# LoRa_V.net
KiCad netlist of a schematic drawn in Altium Designer
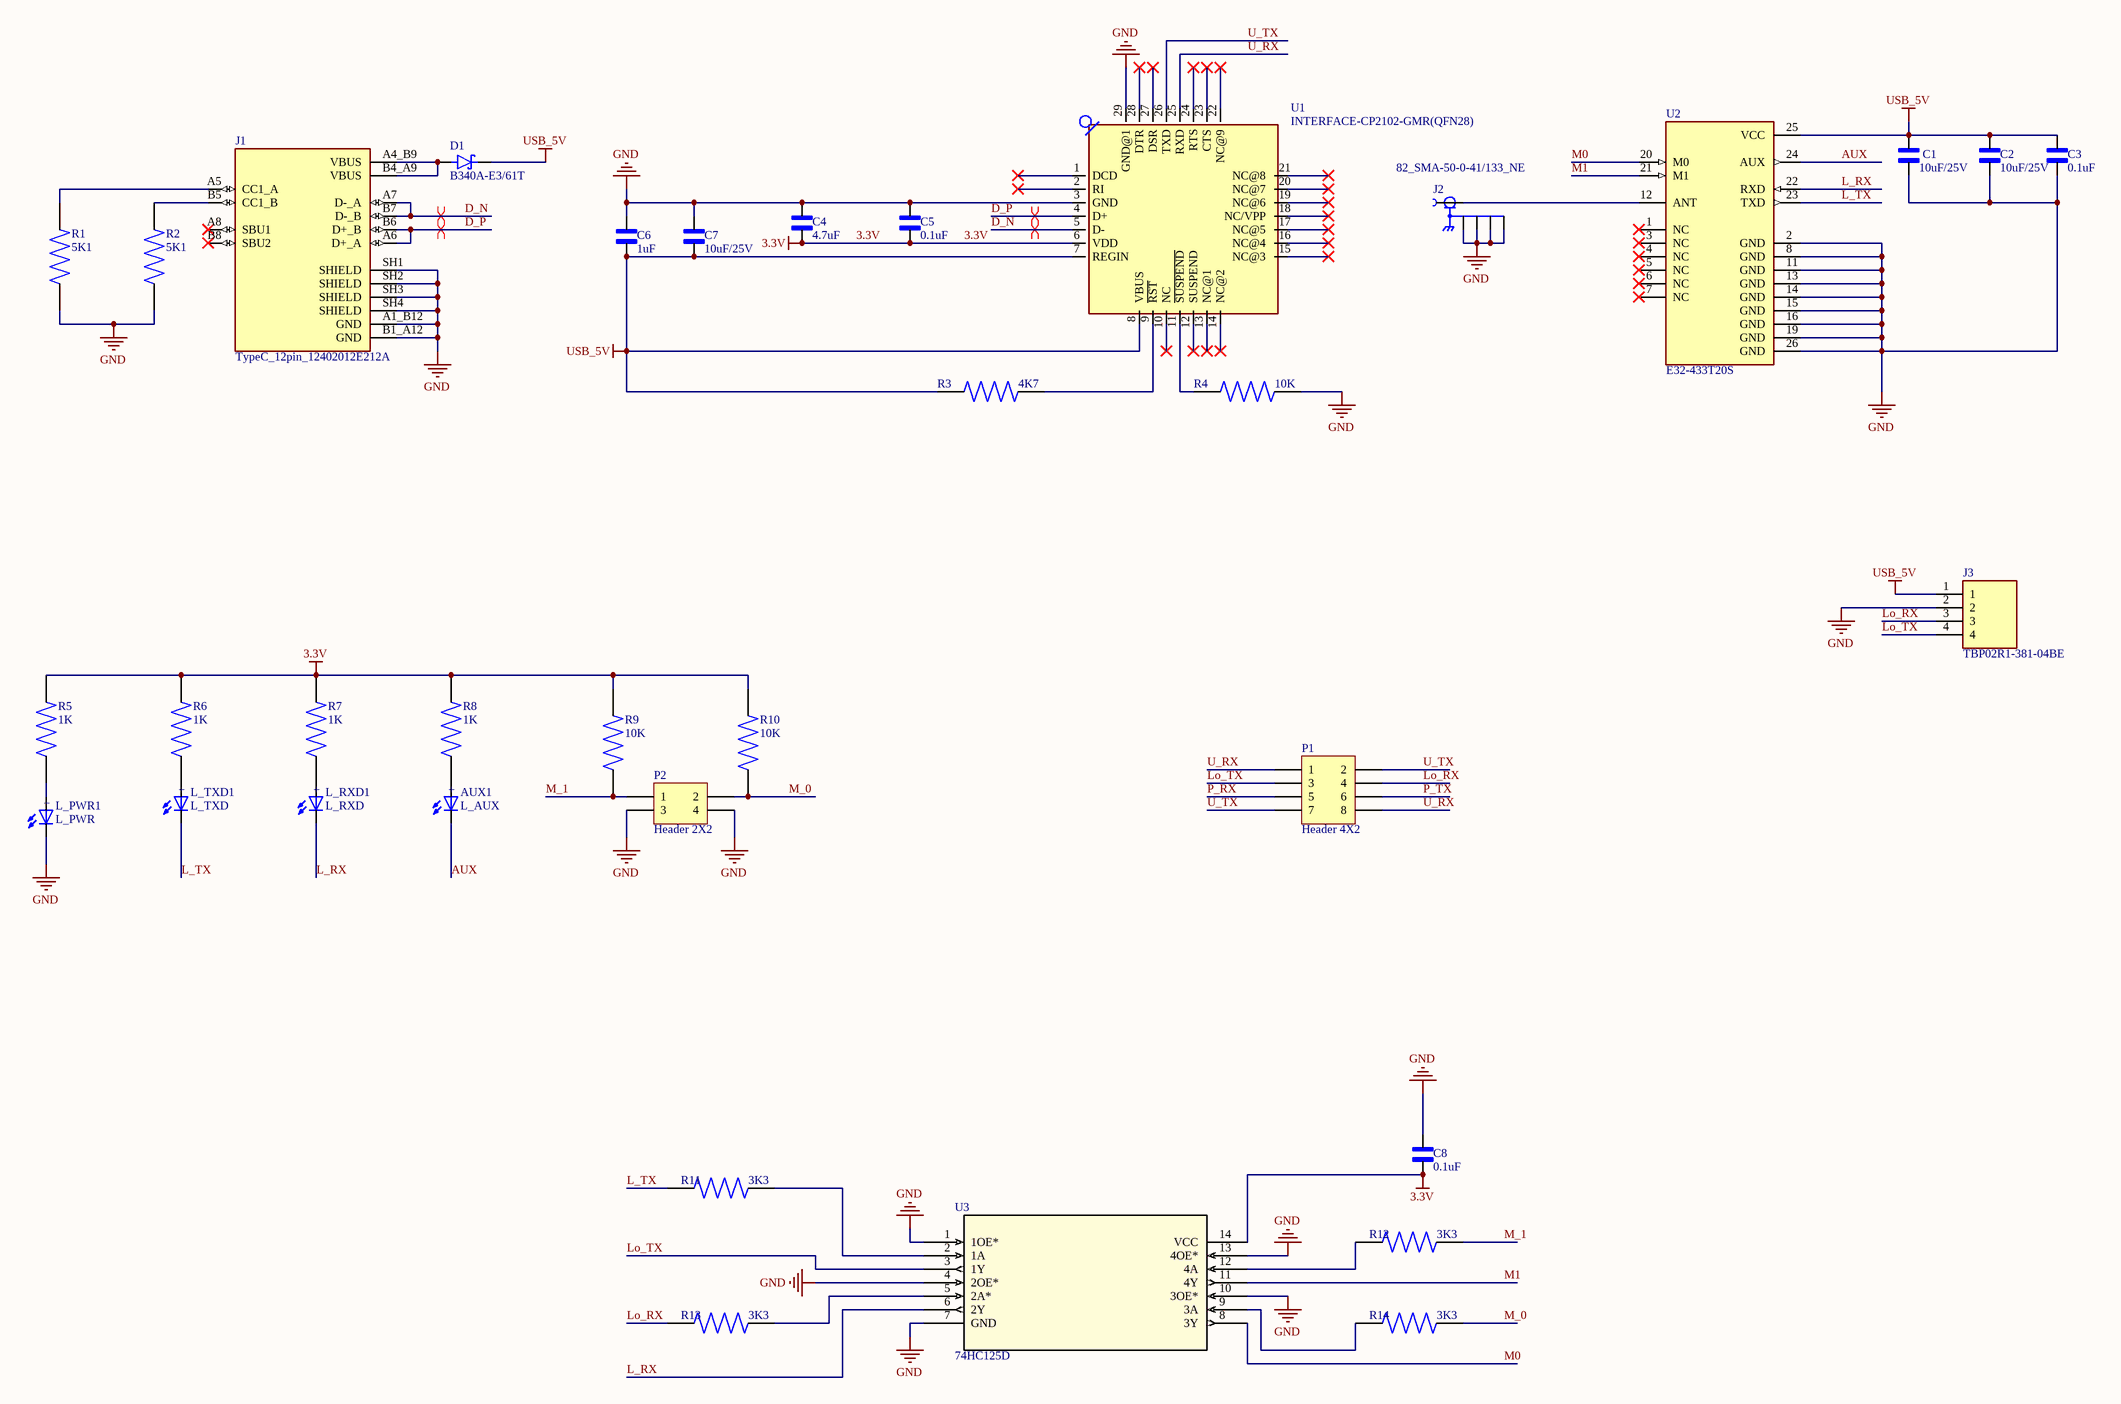
[diagram p0: LoRa_V.SchDoc]

(export (version "E")
  (design (tool "Eeschema 10.0.6"))
  (components
    (comp (ref "AUX1")
      (value "L_AUX")
      (footprint "WL-SMCW_1206")
      (description "1206, Blue Typ.(@20mA): 470nm, 145mcd, 3.2V, 140Â° InGaN")
      (fields (field (name "MF") "Wurth Electronics") (field (name "MP") "150120BS75000"))
      (libsource (lib "VIETTIEN") (part "WL-SMCW_1206"))
    )
    (comp (ref "C1")
      (value "10uF/25V")
      (footprint "CAPC1608X94N")
      (description "cap 0603 (1608 Metric)")
      (fields (field (name "MF") "Vishay Vitramon") (field (name "MP") "VJ0603D3R9DXCAP"))
      (libsource (lib "") (part "cap_0603_VJ0603D3R9DXCAP_1"))
    )
    (comp (ref "C2")
      (value "10uF/25V")
      (footprint "CAPC1608X94N")
      (description "cap 0603 (1608 Metric)")
      (fields (field (name "MF") "Vishay Vitramon") (field (name "MP") "VJ0603D3R9DXCAP"))
      (libsource (lib "") (part "cap_0603_VJ0603D3R9DXCAP_1"))
    )
    (comp (ref "C3")
      (value "0.1uF")
      (footprint "CAPC1608X94N")
      (description "cap 0603 (1608 Metric)")
      (fields (field (name "MF") "Vishay Vitramon") (field (name "MP") "VJ0603D3R9DXCAP"))
      (libsource (lib "") (part "cap_0603_VJ0603D3R9DXCAP_1"))
    )
    (comp (ref "C4")
      (value "4.7uF")
      (footprint "CAPC1608X94N")
      (description "cap 0603 (1608 Metric)")
      (fields (field (name "MF") "Vishay Vitramon") (field (name "MP") "VJ0603D3R9DXCAP"))
      (libsource (lib "") (part "cap_0603_VJ0603D3R9DXCAP_1"))
    )
    (comp (ref "C5")
      (value "0.1uF")
      (footprint "CAPC1608X94N")
      (description "cap 0603 (1608 Metric)")
      (fields (field (name "MF") "Vishay Vitramon") (field (name "MP") "VJ0603D3R9DXCAP"))
      (libsource (lib "") (part "cap_0603_VJ0603D3R9DXCAP_1"))
    )
    (comp (ref "C6")
      (value "1uF")
      (footprint "CAPC1608X94N")
      (description "cap 0603 (1608 Metric)")
      (fields (field (name "MF") "Vishay Vitramon") (field (name "MP") "VJ0603D3R9DXCAP"))
      (libsource (lib "") (part "cap_0603_VJ0603D3R9DXCAP_1"))
    )
    (comp (ref "C7")
      (value "10uF/25V")
      (footprint "CAPC1608X94N")
      (description "cap 0603 (1608 Metric)")
      (fields (field (name "MF") "Vishay Vitramon") (field (name "MP") "VJ0603D3R9DXCAP"))
      (libsource (lib "") (part "cap_0603_VJ0603D3R9DXCAP_1"))
    )
    (comp (ref "C8")
      (value "0.1uF")
      (footprint "CAPC1608X94N")
      (description "cap 0603 (1608 Metric)")
      (fields (field (name "MF") "Vishay Vitramon") (field (name "MP") "VJ0603D3R9DXCAP"))
      (libsource (lib "VIETTIEN") (part "cap_0603_VJ0603D3R9DXCAP"))
    )
    (comp (ref "D1")
      (value "B340A-E3/61T")
      (footprint "DIOM5126X229N")
      (description "Diode Schottky 40 V 3A Surface Mount DO-214AC (SMA)")
      (fields (field (name "MF") "Vishay Semiconductor"))
      (libsource (lib "VIETTIEN") (part "B340A-E3/61T"))
    )
    (comp (ref "J1")
      (value "TypeC_12pin_12402012E212A")
      (footprint "TypeC_12pin_12402012E212A")
      (description "USB2.0, Type C, Top mount, CH 1.68mm, Dual Row SMT")
      (fields (field (name "MP") "12402012E212A") (field (name "MF") "Amphenol ICC (Commercial Products)"))
      (libsource (lib "VIETTIEN") (part "TypeC_12pin_12402012E212A"))
    )
    (comp (ref "J2")
      (value "82_SMA-50-0-41/133_NE")
      (footprint "HUBER+SUHNER_82_SMA-50-0-41/133_NE")
      (description "RF Connectors / Coaxial Connectors, Straight Pcb Jack ¦ HUBER+SUHNER 82_SMA-50-0-41/133_NE")
      (fields (field (name "MF") "HUBER+SUHNER"))
      (libsource (lib "VIETTIEN") (part "82_SMA-50-0-41/133_NE"))
    )
    (comp (ref "J3")
      (value "TBP02R1-381-04BE")
      (footprint "CUI_TBP02R1-381-04BE")
      (description "2~24 Poles, Pluggable,Receptacle, Horizontal, 3.81 Pitch, Terminal Block Connector")
      (fields (field (name "MF") "Same Sky"))
      (libsource (lib "VIETTIEN") (part "TBP02R1-381-04BE"))
    )
    (comp (ref "L_PWR1")
      (value "L_PWR")
      (footprint "WL-SMCW_1206")
      (description "1206, Blue Typ.(@20mA): 470nm, 145mcd, 3.2V, 140Â° InGaN")
      (fields (field (name "MF") "Wurth Electronics") (field (name "MP") "150120BS75000"))
      (libsource (lib "VIETTIEN") (part "WL-SMCW_1206"))
    )
    (comp (ref "L_RXD1")
      (value "L_RXD")
      (footprint "WL-SMCW_1206")
      (description "1206, Blue Typ.(@20mA): 470nm, 145mcd, 3.2V, 140Â° InGaN")
      (fields (field (name "MF") "Wurth Electronics") (field (name "MP") "150120BS75000"))
      (libsource (lib "VIETTIEN") (part "WL-SMCW_1206"))
    )
    (comp (ref "L_TXD1")
      (value "L_TXD")
      (footprint "WL-SMCW_1206")
      (description "1206, Blue Typ.(@20mA): 470nm, 145mcd, 3.2V, 140Â° InGaN")
      (fields (field (name "MF") "Wurth Electronics") (field (name "MP") "150120BS75000"))
      (libsource (lib "VIETTIEN") (part "WL-SMCW_1206"))
    )
    (comp (ref "P1")
      (value "Header 4X2")
      (footprint "HDR2X4")
      (description "Header, 4-Pin, Dual row")
      (fields (field (name "PUBLISHER") "Altium Limited"))
      (libsource (lib "Miscellaneous Connectors") (part "Header 4X2"))
    )
    (comp (ref "P2")
      (value "Header 2X2")
      (footprint "HDR2X2")
      (description "Header, 2-Pin, Dual row")
      (fields (field (name "PUBLISHER") "Altium Limited"))
      (libsource (lib "Miscellaneous Connectors") (part "Header 2X2"))
    )
    (comp (ref "R1")
      (value "5K1")
      (footprint "RES_ERJU03J474V")
      (description "0603 Anti-Sulfurated")
      (fields (field (name "MF") "Panasonic") (field (name "MP") "ERJU03J474V"))
      (libsource (lib "VIETTIEN") (part "res_0603_ERJU03J474V"))
    )
    (comp (ref "R2")
      (value "5K1")
      (footprint "RES_ERJU03J474V")
      (description "0603 Anti-Sulfurated")
      (fields (field (name "MF") "Panasonic") (field (name "MP") "ERJU03J474V"))
      (libsource (lib "VIETTIEN") (part "res_0603_ERJU03J474V"))
    )
    (comp (ref "R3")
      (value "4K7")
      (footprint "RES_ERJU03J474V")
      (description "0603 Anti-Sulfurated")
      (fields (field (name "MF") "Panasonic") (field (name "MP") "ERJU03J474V"))
      (libsource (lib "VIETTIEN") (part "res_0603_ERJU03J474V"))
    )
    (comp (ref "R4")
      (value "10K")
      (footprint "RES_ERJU03J474V")
      (description "0603 Anti-Sulfurated")
      (fields (field (name "MF") "Panasonic") (field (name "MP") "ERJU03J474V"))
      (libsource (lib "VIETTIEN") (part "res_0603_ERJU03J474V"))
    )
    (comp (ref "R5")
      (value "1K")
      (footprint "RES_ERJU03J474V")
      (description "0603 Anti-Sulfurated")
      (fields (field (name "MF") "Panasonic") (field (name "MP") "ERJU03J474V"))
      (libsource (lib "VIETTIEN") (part "res_0603_ERJU03J474V"))
    )
    (comp (ref "R6")
      (value "1K")
      (footprint "RES_ERJU03J474V")
      (description "0603 Anti-Sulfurated")
      (fields (field (name "MF") "Panasonic") (field (name "MP") "ERJU03J474V"))
      (libsource (lib "VIETTIEN") (part "res_0603_ERJU03J474V"))
    )
    (comp (ref "R7")
      (value "1K")
      (footprint "RES_ERJU03J474V")
      (description "0603 Anti-Sulfurated")
      (fields (field (name "MF") "Panasonic") (field (name "MP") "ERJU03J474V"))
      (libsource (lib "VIETTIEN") (part "res_0603_ERJU03J474V"))
    )
    (comp (ref "R8")
      (value "1K")
      (footprint "RES_ERJU03J474V")
      (description "0603 Anti-Sulfurated")
      (fields (field (name "MF") "Panasonic") (field (name "MP") "ERJU03J474V"))
      (libsource (lib "VIETTIEN") (part "res_0603_ERJU03J474V"))
    )
    (comp (ref "R9")
      (value "10K")
      (footprint "RES_ERJU03J474V")
      (description "0603 Anti-Sulfurated")
      (fields (field (name "MF") "Panasonic") (field (name "MP") "ERJU03J474V"))
      (libsource (lib "VIETTIEN") (part "res_0603_ERJU03J474V"))
    )
    (comp (ref "R10")
      (value "10K")
      (footprint "RES_ERJU03J474V")
      (description "0603 Anti-Sulfurated")
      (fields (field (name "MF") "Panasonic") (field (name "MP") "ERJU03J474V"))
      (libsource (lib "VIETTIEN") (part "res_0603_ERJU03J474V"))
    )
    (comp (ref "R11")
      (value "3K3")
      (footprint "RES_ERJU03J474V")
      (description "0603 Anti-Sulfurated")
      (fields (field (name "MF") "Panasonic") (field (name "MP") "ERJU03J474V"))
      (libsource (lib "VIETTIEN") (part "res_0603_ERJU03J474V"))
    )
    (comp (ref "R12")
      (value "3K3")
      (footprint "RES_ERJU03J474V")
      (description "0603 Anti-Sulfurated")
      (fields (field (name "MF") "Panasonic") (field (name "MP") "ERJU03J474V"))
      (libsource (lib "VIETTIEN") (part "res_0603_ERJU03J474V"))
    )
    (comp (ref "R13")
      (value "3K3")
      (footprint "RES_ERJU03J474V")
      (description "0603 Anti-Sulfurated")
      (fields (field (name "MF") "Panasonic") (field (name "MP") "ERJU03J474V"))
      (libsource (lib "VIETTIEN") (part "res_0603_ERJU03J474V"))
    )
    (comp (ref "R14")
      (value "3K3")
      (footprint "RES_ERJU03J474V")
      (description "0603 Anti-Sulfurated")
      (fields (field (name "MF") "Panasonic") (field (name "MP") "ERJU03J474V"))
      (libsource (lib "VIETTIEN") (part "res_0603_ERJU03J474V"))
    )
    (comp (ref "U1")
      (value "INTERFACE-CP2102-GMR(QFN28)")
      (footprint "QFN28G_0.5-5X5MM")
      (description "USB Bridge, USB to UART USB 2.0 UART Interface 28-QFN (5x5)")
      (fields (field (name "MP") "CP2102-GMR") (field (name "MF") "Silicon"))
      (libsource (lib "VIETTIEN") (part "INTERFACE-CP2102-GMR(QFN28)"))
    )
    (comp (ref "U2")
      (value "E32-433T20S")
      (footprint "MODULE_E32-433T20S")
      (description "Wireless serial port module (UART)")
      (fields (field (name "MF") "EBYTE"))
      (libsource (lib "VIETTIEN") (part "E32-433T20S"))
    )
    (comp (ref "U3")
      (value "74HC125D")
      (footprint "SOT108-1_NEX")
      (description "Description")
      (fields (field (name "COPYRIGHT") "Copyright (C) 2025 Ultra Librarian. All rights reserved."))
      (libsource (lib "VIETTIEN") (part "74HC125D"))
    )
  )
  (nets
    (net (code "1") (name "/AUX") (class "Default")
      (node (ref "AUX1") (pin "1") (pinfunction "NEG_1") (pintype "passive"))
      (node (ref "U2") (pin "24") (pinfunction "AUX_24") (pintype "output"))
    )
    (net (code "2") (name "/D_N") (class "Default")
      (node (ref "J1") (pin "A7") (pinfunction "D-_A_A7") (pintype "bidirectional"))
      (node (ref "J1") (pin "B7") (pinfunction "D-_B_B7") (pintype "bidirectional"))
      (node (ref "U1") (pin "5") (pinfunction "D-_5") (pintype "bidirectional"))
    )
    (net (code "3") (name "/D_P") (class "Default")
      (node (ref "J1") (pin "A6") (pinfunction "D+_A_A6") (pintype "bidirectional"))
      (node (ref "J1") (pin "B6") (pinfunction "D+_B_B6") (pintype "bidirectional"))
      (node (ref "U1") (pin "4") (pinfunction "D+_4") (pintype "bidirectional"))
    )
    (net (code "4") (name "/L_RX") (class "Default")
      (node (ref "L_RXD1") (pin "1") (pinfunction "NEG_1") (pintype "passive"))
      (node (ref "U2") (pin "22") (pinfunction "RXD_22") (pintype "input"))
      (node (ref "U3") (pin "6") (pinfunction "2Y_6") (pintype "output"))
    )
    (net (code "5") (name "/L_TX") (class "Default")
      (node (ref "L_TXD1") (pin "1") (pinfunction "NEG_1") (pintype "passive"))
      (node (ref "R11") (pin "1") (pinfunction "1_1") (pintype "passive"))
      (node (ref "U2") (pin "23") (pinfunction "TXD_23") (pintype "output"))
    )
    (net (code "6") (name "/Lo_RX") (class "Default")
      (node (ref "J3") (pin "3") (pinfunction "3_3") (pintype "passive"))
      (node (ref "P1") (pin "4") (pinfunction "4_4") (pintype "passive"))
      (node (ref "R13") (pin "1") (pinfunction "1_1") (pintype "passive"))
    )
    (net (code "7") (name "/Lo_TX") (class "Default")
      (node (ref "J3") (pin "4") (pinfunction "4_4") (pintype "passive"))
      (node (ref "P1") (pin "3") (pinfunction "3_3") (pintype "passive"))
      (node (ref "U3") (pin "3") (pinfunction "1Y_3") (pintype "output"))
    )
    (net (code "8") (name "/M0") (class "Default")
      (node (ref "U2") (pin "20") (pinfunction "M0_20") (pintype "input"))
      (node (ref "U3") (pin "8") (pinfunction "3Y_8") (pintype "output"))
    )
    (net (code "9") (name "/M1") (class "Default")
      (node (ref "U2") (pin "21") (pinfunction "M1_21") (pintype "input"))
      (node (ref "U3") (pin "11") (pinfunction "4Y_11") (pintype "output"))
    )
    (net (code "10") (name "/M_0") (class "Default")
      (node (ref "P2") (pin "2") (pinfunction "2_2") (pintype "passive"))
      (node (ref "R10") (pin "2") (pinfunction "2_2") (pintype "passive"))
      (node (ref "R14") (pin "2") (pinfunction "2_2") (pintype "passive"))
    )
    (net (code "11") (name "/M_1") (class "Default")
      (node (ref "P2") (pin "1") (pinfunction "1_1") (pintype "passive"))
      (node (ref "R12") (pin "2") (pinfunction "2_2") (pintype "passive"))
      (node (ref "R9") (pin "2") (pinfunction "2_2") (pintype "passive"))
    )
    (net (code "12") (name "/P_RX") (class "Default")
      (node (ref "P1") (pin "5") (pinfunction "5_5") (pintype "passive"))
    )
    (net (code "13") (name "/P_TX") (class "Default")
      (node (ref "P1") (pin "6") (pinfunction "6_6") (pintype "passive"))
    )
    (net (code "14") (name "/U_RX") (class "Default")
      (node (ref "P1") (pin "1") (pinfunction "1_1") (pintype "passive"))
      (node (ref "P1") (pin "8") (pinfunction "8_8") (pintype "passive"))
      (node (ref "U1") (pin "25") (pinfunction "RXD_25") (pintype "bidirectional"))
    )
    (net (code "15") (name "/U_TX") (class "Default")
      (node (ref "P1") (pin "2") (pinfunction "2_2") (pintype "passive"))
      (node (ref "P1") (pin "7") (pinfunction "7_7") (pintype "passive"))
      (node (ref "U1") (pin "26") (pinfunction "TXD_26") (pintype "bidirectional"))
    )
    (net (code "16") (name "3.3V") (class "Default")
      (node (ref "C4") (pin "1") (pinfunction "1_1") (pintype "passive"))
      (node (ref "C5") (pin "1") (pinfunction "1_1") (pintype "passive"))
      (node (ref "C8") (pin "2") (pinfunction "2_2") (pintype "passive"))
      (node (ref "R10") (pin "1") (pinfunction "1_1") (pintype "passive"))
      (node (ref "R5") (pin "2") (pinfunction "2_2") (pintype "passive"))
      (node (ref "R6") (pin "2") (pinfunction "2_2") (pintype "passive"))
      (node (ref "R7") (pin "2") (pinfunction "2_2") (pintype "passive"))
      (node (ref "R8") (pin "2") (pinfunction "2_2") (pintype "passive"))
      (node (ref "R9") (pin "1") (pinfunction "1_1") (pintype "passive"))
      (node (ref "U1") (pin "6") (pinfunction "VDD_6") (pintype "bidirectional"))
      (node (ref "U3") (pin "14") (pinfunction "VCC_14") (pintype "power_in"))
    )
    (net (code "17") (name "GND") (class "Default")
      (node (ref "C1") (pin "1") (pinfunction "1_1") (pintype "passive"))
      (node (ref "C2") (pin "1") (pinfunction "1_1") (pintype "passive"))
      (node (ref "C3") (pin "1") (pinfunction "1_1") (pintype "passive"))
      (node (ref "C4") (pin "2") (pinfunction "2_2") (pintype "passive"))
      (node (ref "C5") (pin "2") (pinfunction "2_2") (pintype "passive"))
      (node (ref "C6") (pin "2") (pinfunction "2_2") (pintype "passive"))
      (node (ref "C7") (pin "2") (pinfunction "2_2") (pintype "passive"))
      (node (ref "C8") (pin "1") (pinfunction "1_1") (pintype "passive"))
      (node (ref "J1") (pin "A1_B12") (pinfunction "GND_A1_B12") (pintype "power_in"))
      (node (ref "J1") (pin "B1_A12") (pinfunction "GND_B1_A12") (pintype "power_in"))
      (node (ref "J1") (pin "SH1") (pinfunction "SHIELD_SH1") (pintype "passive"))
      (node (ref "J1") (pin "SH2") (pinfunction "SHIELD_SH2") (pintype "passive"))
      (node (ref "J1") (pin "SH3") (pinfunction "SHIELD_SH3") (pintype "passive"))
      (node (ref "J1") (pin "SH4") (pinfunction "SHIELD_SH4") (pintype "passive"))
      (node (ref "J2") (pin "G1") (pinfunction "G1_G1") (pintype "power_in"))
      (node (ref "J2") (pin "G2") (pinfunction "G2_G2") (pintype "power_in"))
      (node (ref "J2") (pin "G3") (pinfunction "G3_G3") (pintype "power_in"))
      (node (ref "J2") (pin "G4") (pinfunction "G4_G4") (pintype "power_in"))
      (node (ref "J3") (pin "2") (pinfunction "2_2") (pintype "passive"))
      (node (ref "L_PWR1") (pin "1") (pinfunction "NEG_1") (pintype "passive"))
      (node (ref "P2") (pin "3") (pinfunction "3_3") (pintype "passive"))
      (node (ref "P2") (pin "4") (pinfunction "4_4") (pintype "passive"))
      (node (ref "R1") (pin "1") (pinfunction "1_1") (pintype "passive"))
      (node (ref "R2") (pin "1") (pinfunction "1_1") (pintype "passive"))
      (node (ref "R4") (pin "2") (pinfunction "2_2") (pintype "passive"))
      (node (ref "U1") (pin "29") (pinfunction "GND@1_29") (pintype "bidirectional"))
      (node (ref "U1") (pin "3") (pinfunction "GND_3") (pintype "bidirectional"))
      (node (ref "U2") (pin "11") (pinfunction "GND_11") (pintype "power_in"))
      (node (ref "U2") (pin "13") (pinfunction "GND_13") (pintype "power_in"))
      (node (ref "U2") (pin "14") (pinfunction "GND_14") (pintype "power_in"))
      (node (ref "U2") (pin "15") (pinfunction "GND_15") (pintype "power_in"))
      (node (ref "U2") (pin "16") (pinfunction "GND_16") (pintype "power_in"))
      (node (ref "U2") (pin "19") (pinfunction "GND_19") (pintype "power_in"))
      (node (ref "U2") (pin "2") (pinfunction "GND_2") (pintype "power_in"))
      (node (ref "U2") (pin "26") (pinfunction "GND_26") (pintype "power_in"))
      (node (ref "U2") (pin "8") (pinfunction "GND_8") (pintype "power_in"))
      (node (ref "U3") (pin "1") (pinfunction "1OE*_1") (pintype "input"))
      (node (ref "U3") (pin "10") (pinfunction "3OE*_10") (pintype "input"))
      (node (ref "U3") (pin "13") (pinfunction "4OE*_13") (pintype "input"))
      (node (ref "U3") (pin "4") (pinfunction "2OE*_4") (pintype "input"))
      (node (ref "U3") (pin "7") (pinfunction "GND_7") (pintype "power_in"))
    )
    (net (code "18") (name "Net-(AUX1-POS)") (class "Default")
      (node (ref "AUX1") (pin "2") (pinfunction "POS_2") (pintype "passive"))
      (node (ref "R8") (pin "1") (pinfunction "1_1") (pintype "passive"))
    )
    (net (code "19") (name "Net-(D1-PadA)") (class "Default")
      (node (ref "D1") (pin "A") (pinfunction "A_A") (pintype "passive"))
      (node (ref "J1") (pin "A4_B9") (pinfunction "VBUS_A4_B9") (pintype "power_in"))
      (node (ref "J1") (pin "B4_A9") (pinfunction "VBUS_B4_A9") (pintype "power_in"))
    )
    (net (code "20") (name "Net-(J1-CC1_A)") (class "Default")
      (node (ref "J1") (pin "A5") (pinfunction "CC1_A_A5") (pintype "bidirectional"))
      (node (ref "R1") (pin "2") (pinfunction "2_2") (pintype "passive"))
    )
    (net (code "21") (name "Net-(J1-CC1_B)") (class "Default")
      (node (ref "J1") (pin "B5") (pinfunction "CC1_B_B5") (pintype "bidirectional"))
      (node (ref "R2") (pin "2") (pinfunction "2_2") (pintype "passive"))
    )
    (net (code "22") (name "Net-(L_PWR1-POS)") (class "Default")
      (node (ref "L_PWR1") (pin "2") (pinfunction "POS_2") (pintype "passive"))
      (node (ref "R5") (pin "1") (pinfunction "1_1") (pintype "passive"))
    )
    (net (code "23") (name "Net-(L_RXD1-POS)") (class "Default")
      (node (ref "L_RXD1") (pin "2") (pinfunction "POS_2") (pintype "passive"))
      (node (ref "R7") (pin "1") (pinfunction "1_1") (pintype "passive"))
    )
    (net (code "24") (name "Net-(L_TXD1-POS)") (class "Default")
      (node (ref "L_TXD1") (pin "2") (pinfunction "POS_2") (pintype "passive"))
      (node (ref "R6") (pin "1") (pinfunction "1_1") (pintype "passive"))
    )
    (net (code "25") (name "Net-(U1-~{RST})") (class "Default")
      (node (ref "R3") (pin "2") (pinfunction "2_2") (pintype "passive"))
      (node (ref "U1") (pin "9") (pinfunction "~{RST}_9") (pintype "bidirectional"))
    )
    (net (code "26") (name "Net-(U1-~{SUSPEND})") (class "Default")
      (node (ref "R4") (pin "1") (pinfunction "1_1") (pintype "passive"))
      (node (ref "U1") (pin "11") (pinfunction "~{SUSPEND}_11") (pintype "bidirectional"))
    )
    (net (code "27") (name "Net-(U2-ANT)") (class "Default")
      (node (ref "J2") (pin "1") (pinfunction "1_1") (pintype "passive"))
      (node (ref "U2") (pin "12") (pinfunction "ANT_12") (pintype "passive"))
    )
    (net (code "28") (name "Net-(U3-1A)") (class "Default")
      (node (ref "R11") (pin "2") (pinfunction "2_2") (pintype "passive"))
      (node (ref "U3") (pin "2") (pinfunction "1A_2") (pintype "input"))
    )
    (net (code "29") (name "Net-(U3-2A*)") (class "Default")
      (node (ref "R13") (pin "2") (pinfunction "2_2") (pintype "passive"))
      (node (ref "U3") (pin "5") (pinfunction "2A*_5") (pintype "input"))
    )
    (net (code "30") (name "Net-(U3-3A)") (class "Default")
      (node (ref "R14") (pin "1") (pinfunction "1_1") (pintype "passive"))
      (node (ref "U3") (pin "9") (pinfunction "3A_9") (pintype "input"))
    )
    (net (code "31") (name "Net-(U3-4A)") (class "Default")
      (node (ref "R12") (pin "1") (pinfunction "1_1") (pintype "passive"))
      (node (ref "U3") (pin "12") (pinfunction "4A_12") (pintype "input"))
    )
    (net (code "32") (name "USB_5V") (class "Default")
      (node (ref "C1") (pin "2") (pinfunction "2_2") (pintype "passive"))
      (node (ref "C2") (pin "2") (pinfunction "2_2") (pintype "passive"))
      (node (ref "C3") (pin "2") (pinfunction "2_2") (pintype "passive"))
      (node (ref "C6") (pin "1") (pinfunction "1_1") (pintype "passive"))
      (node (ref "C7") (pin "1") (pinfunction "1_1") (pintype "passive"))
      (node (ref "D1") (pin "C") (pinfunction "C_C") (pintype "passive"))
      (node (ref "J3") (pin "1") (pinfunction "1_1") (pintype "passive"))
      (node (ref "R3") (pin "1") (pinfunction "1_1") (pintype "passive"))
      (node (ref "U1") (pin "7") (pinfunction "REGIN_7") (pintype "bidirectional"))
      (node (ref "U1") (pin "8") (pinfunction "VBUS_8") (pintype "bidirectional"))
      (node (ref "U2") (pin "25") (pinfunction "VCC_25") (pintype "power_in"))
    )
    (net (code "33") (name "unconnected-(J1-SBU1-PadA8)") (class "Default")
      (node (ref "J1") (pin "A8") (pinfunction "SBU1_A8") (pintype "bidirectional+no_connect"))
    )
    (net (code "34") (name "unconnected-(J1-SBU2-PadB8)") (class "Default")
      (node (ref "J1") (pin "B8") (pinfunction "SBU2_B8") (pintype "bidirectional+no_connect"))
    )
    (net (code "35") (name "unconnected-(U1-CTS-Pad23)") (class "Default")
      (node (ref "U1") (pin "23") (pinfunction "CTS_23") (pintype "bidirectional+no_connect"))
    )
    (net (code "36") (name "unconnected-(U1-DCD-Pad1)") (class "Default")
      (node (ref "U1") (pin "1") (pinfunction "DCD_1") (pintype "bidirectional+no_connect"))
    )
    (net (code "37") (name "unconnected-(U1-DSR-Pad27)") (class "Default")
      (node (ref "U1") (pin "27") (pinfunction "DSR_27") (pintype "bidirectional+no_connect"))
    )
    (net (code "38") (name "unconnected-(U1-DTR-Pad28)") (class "Default")
      (node (ref "U1") (pin "28") (pinfunction "DTR_28") (pintype "bidirectional+no_connect"))
    )
    (net (code "39") (name "unconnected-(U1-NC-Pad10)") (class "Default")
      (node (ref "U1") (pin "10") (pinfunction "NC_10") (pintype "bidirectional+no_connect"))
    )
    (net (code "40") (name "unconnected-(U1-NC@1-Pad13)") (class "Default")
      (node (ref "U1") (pin "13") (pinfunction "NC@1_13") (pintype "bidirectional+no_connect"))
    )
    (net (code "41") (name "unconnected-(U1-NC@2-Pad14)") (class "Default")
      (node (ref "U1") (pin "14") (pinfunction "NC@2_14") (pintype "bidirectional+no_connect"))
    )
    (net (code "42") (name "unconnected-(U1-NC@3-Pad15)") (class "Default")
      (node (ref "U1") (pin "15") (pinfunction "NC@3_15") (pintype "bidirectional+no_connect"))
    )
    (net (code "43") (name "unconnected-(U1-NC@4-Pad16)") (class "Default")
      (node (ref "U1") (pin "16") (pinfunction "NC@4_16") (pintype "bidirectional+no_connect"))
    )
    (net (code "44") (name "unconnected-(U1-NC@5-Pad17)") (class "Default")
      (node (ref "U1") (pin "17") (pinfunction "NC@5_17") (pintype "bidirectional+no_connect"))
    )
    (net (code "45") (name "unconnected-(U1-NC@6-Pad19)") (class "Default")
      (node (ref "U1") (pin "19") (pinfunction "NC@6_19") (pintype "bidirectional+no_connect"))
    )
    (net (code "46") (name "unconnected-(U1-NC@7-Pad20)") (class "Default")
      (node (ref "U1") (pin "20") (pinfunction "NC@7_20") (pintype "bidirectional+no_connect"))
    )
    (net (code "47") (name "unconnected-(U1-NC@8-Pad21)") (class "Default")
      (node (ref "U1") (pin "21") (pinfunction "NC@8_21") (pintype "bidirectional+no_connect"))
    )
    (net (code "48") (name "unconnected-(U1-NC@9-Pad22)") (class "Default")
      (node (ref "U1") (pin "22") (pinfunction "NC@9_22") (pintype "bidirectional+no_connect"))
    )
    (net (code "49") (name "unconnected-(U1-NC{slash}VPP-Pad18)") (class "Default")
      (node (ref "U1") (pin "18") (pinfunction "NC/VPP_18") (pintype "bidirectional+no_connect"))
    )
    (net (code "50") (name "unconnected-(U1-RI-Pad2)") (class "Default")
      (node (ref "U1") (pin "2") (pinfunction "RI_2") (pintype "bidirectional+no_connect"))
    )
    (net (code "51") (name "unconnected-(U1-RTS-Pad24)") (class "Default")
      (node (ref "U1") (pin "24") (pinfunction "RTS_24") (pintype "bidirectional+no_connect"))
    )
    (net (code "52") (name "unconnected-(U1-SUSPEND-Pad12)") (class "Default")
      (node (ref "U1") (pin "12") (pinfunction "SUSPEND_12") (pintype "bidirectional+no_connect"))
    )
    (net (code "53") (name "unconnected-(U2-NC-Pad1)") (class "Default")
      (node (ref "U2") (pin "1") (pinfunction "NC_1") (pintype "passive+no_connect"))
    )
    (net (code "54") (name "unconnected-(U2-NC-Pad3)") (class "Default")
      (node (ref "U2") (pin "3") (pinfunction "NC_3") (pintype "passive+no_connect"))
    )
    (net (code "55") (name "unconnected-(U2-NC-Pad4)") (class "Default")
      (node (ref "U2") (pin "4") (pinfunction "NC_4") (pintype "passive+no_connect"))
    )
    (net (code "56") (name "unconnected-(U2-NC-Pad5)") (class "Default")
      (node (ref "U2") (pin "5") (pinfunction "NC_5") (pintype "passive+no_connect"))
    )
    (net (code "57") (name "unconnected-(U2-NC-Pad6)") (class "Default")
      (node (ref "U2") (pin "6") (pinfunction "NC_6") (pintype "passive+no_connect"))
    )
    (net (code "58") (name "unconnected-(U2-NC-Pad7)") (class "Default")
      (node (ref "U2") (pin "7") (pinfunction "NC_7") (pintype "passive+no_connect"))
    )
  )
)
